# Driver_Motor_Sheet.net
KiCad netlist of a schematic drawn in Altium Designer
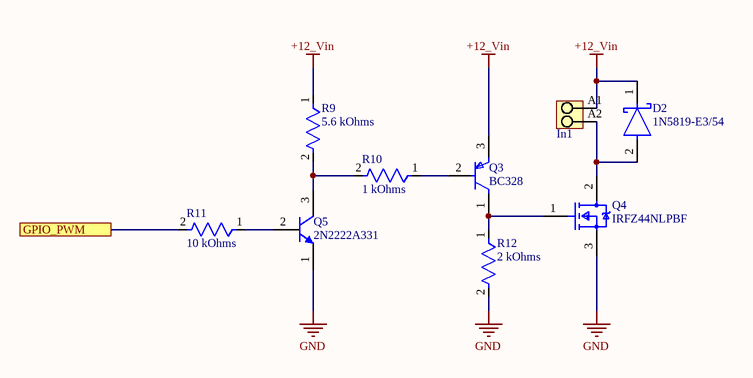
[diagram p0: Driver_Motor_Sheet.SchDoc]

(export (version "E")
  (design (tool "Eeschema 10.0.6"))
  (components
    (comp (ref "D2")
      (value "1N5819-E3/54")
      (footprint "FP-1N5819-E3-54-MFG")
      (description "DIODE SCHOTTKY 40V 1A DO204AL")
      (fields (field (name "VOLTAGE") "40V"))
      (libsource (lib "Altium Content Vault") (part "1d6ec82d83fb6aee721767c19dac4b9"))
    )
    (comp (ref "In1")
      (value "1715310000")
      (footprint "LM_5_00_90_02")
      (description "OMNIMATE Signal - series LM")
      (fields (field (name "MANUFACTURER") "Weidmueller"))
      (libsource (lib "Altium Content Vault") (part "Terminal_02_1x02"))
    )
    (comp (ref "Q3") (value "BC328") (footprint "TO-92") (libsource (lib "Own_Linrary") (part "BC328")))
    (comp (ref "Q4")
      (value "IRFZ44NLPBF")
      (footprint "FP-PG-TO262-3-MFG")
      (description "IRFZ44NLPBF Single N-Channel 55 V 17.5 mOhm 63 nC HEXFET® Power Mosfet - TO-262")
      (libsource (lib "Altium Content Vault") (part "b09f7f152735e370c1ea22a33fa83d6"))
    )
    (comp (ref "Q5")
      (value "2N2222A331")
      (footprint "TO-92")
      (fields (field (name "MANUFACTURER") "Multicomp") (field (name "MANUFACTURER PART NUMBER") "2N2222"))
      (libsource (lib "Own_Linrary") (part "2N2222A331"))
    )
    (comp (ref "R9")
      (value "5.6 kOhms")
      (footprint "FP-FMP100-MFG")
      (description "Resistor, 1 kOhm, ± 5%, 1 W, Axial Leaded, Metal Film, High Power Flame Proof")
      (fields (field (name "TOLERANCE") "5%"))
      (libsource (lib "Altium Content Vault") (part "FMP100JT-52-1K"))
    )
    (comp (ref "R10")
      (value "1 kOhms")
      (footprint "FP-FMP100-MFG")
      (description "Resistor, 1 kOhm, ± 5%, 1 W, Axial Leaded, Metal Film, High Power Flame Proof")
      (fields (field (name "TOLERANCE") "5%"))
      (libsource (lib "Altium Content Vault") (part "FMP100JT-52-1K"))
    )
    (comp (ref "R11")
      (value "10 kOhms")
      (footprint "FP-FMP100-MFG")
      (description "Resistor, 1 kOhm, ± 5%, 1 W, Axial Leaded, Metal Film, High Power Flame Proof")
      (fields (field (name "TOLERANCE") "5%"))
      (libsource (lib "Altium Content Vault") (part "FMP100JT-52-1K"))
    )
    (comp (ref "R12")
      (value "2 kOhms")
      (footprint "FP-FMP100-MFG")
      (description "Resistor, 1 kOhm, ± 5%, 1 W, Axial Leaded, Metal Film, High Power Flame Proof")
      (fields (field (name "TOLERANCE") "5%"))
      (libsource (lib "Altium Content Vault") (part "FMP100JT-52-1K"))
    )
  )
  (nets
    (net (code "1") (name "+12_Vin") (class "Default")
      (node (ref "D2") (pin "1") (pinfunction "C_1") (pintype "passive"))
      (node (ref "In1") (pin "A1") (pinfunction "A1_A1") (pintype "passive"))
      (node (ref "Q3") (pin "3") (pinfunction "C_3") (pintype "passive"))
      (node (ref "R9") (pin "1") (pinfunction "1_1") (pintype "passive"))
    )
    (net (code "2") (name "/GPIO_PWM") (class "Default")
      (node (ref "R11") (pin "2") (pinfunction "2_2") (pintype "passive"))
    )
    (net (code "3") (name "GND") (class "Default")
      (node (ref "Q4") (pin "3") (pinfunction "S_3") (pintype "passive"))
      (node (ref "Q5") (pin "1") (pinfunction "E_1") (pintype "passive"))
      (node (ref "R12") (pin "2") (pinfunction "2_2") (pintype "passive"))
    )
    (net (code "4") (name "Net-(D2-A)") (class "Default")
      (node (ref "D2") (pin "2") (pinfunction "A_2") (pintype "passive"))
      (node (ref "In1") (pin "A2") (pinfunction "A2_A2") (pintype "passive"))
      (node (ref "Q4") (pin "2") (pinfunction "D_2") (pintype "passive"))
    )
    (net (code "5") (name "Net-(Q3-B)") (class "Default")
      (node (ref "Q3") (pin "2") (pinfunction "B_2") (pintype "passive"))
      (node (ref "R10") (pin "1") (pinfunction "1_1") (pintype "passive"))
    )
    (net (code "6") (name "Net-(Q3-E)") (class "Default")
      (node (ref "Q3") (pin "1") (pinfunction "E_1") (pintype "passive"))
      (node (ref "Q4") (pin "1") (pinfunction "G_1") (pintype "passive"))
      (node (ref "R12") (pin "1") (pinfunction "1_1") (pintype "passive"))
    )
    (net (code "7") (name "Net-(Q5-B)") (class "Default")
      (node (ref "Q5") (pin "2") (pinfunction "B_2") (pintype "passive"))
      (node (ref "R11") (pin "1") (pinfunction "1_1") (pintype "passive"))
    )
    (net (code "8") (name "Net-(Q5-C)") (class "Default")
      (node (ref "Q5") (pin "3") (pinfunction "C_3") (pintype "passive"))
      (node (ref "R10") (pin "2") (pinfunction "2_2") (pintype "passive"))
      (node (ref "R9") (pin "2") (pinfunction "2_2") (pintype "passive"))
    )
  )
)
